# MSP430.net
KiCad netlist of a schematic drawn in Altium Designer
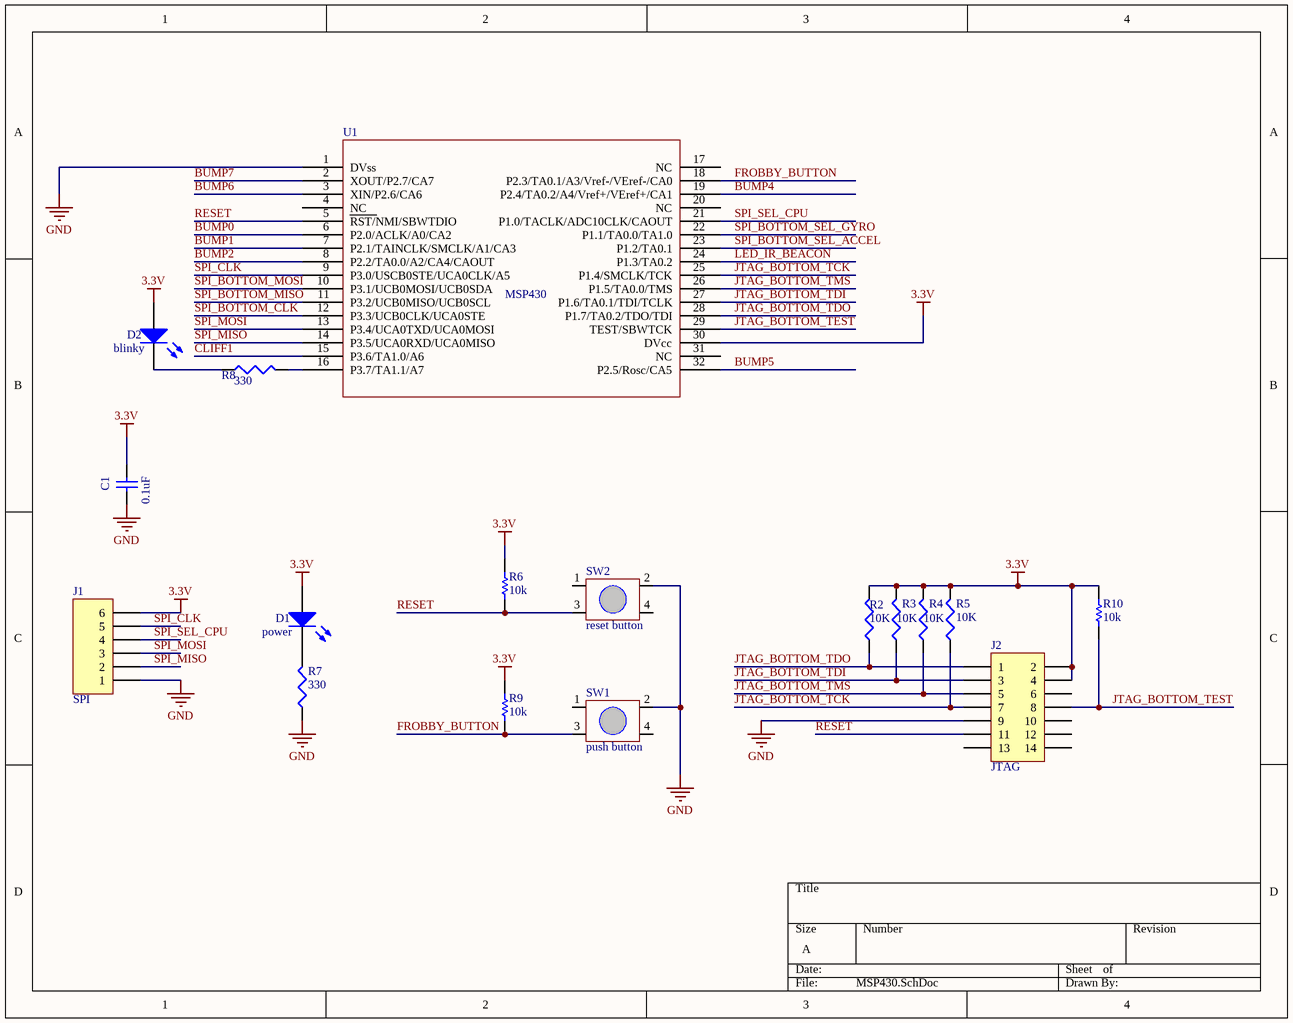
[diagram p0: MSP430.SchDoc]

(export (version "E")
  (design (tool "Eeschema 10.0.6"))
  (components
    (comp (ref "C1")
      (value "0.1uF")
      (footprint "CAPC1005L")
      (description "Capacitor (Semiconductor SIM Model)")
      (fields (field (name "Comment") "Cap Semi") (field (name "PUBLISHER") "Altium Limited"))
      (libsource (lib "Miscellaneous Devices") (part "Cap Semi"))
    )
    (comp (ref "D1") (value "power") (footprint "INDC2012L") (libsource (lib "mrone") (part "LED")))
    (comp (ref "D2") (value "blinky") (footprint "INDC2012L") (libsource (lib "mrone") (part "LED")))
    (comp (ref "J1")
      (value "SPI")
      (footprint "HDR1X6")
      (description "Header, 6-Pin")
      (fields (field (name "PUBLISHER") "Altium Limited"))
      (libsource (lib "Miscellaneous Connectors") (part "Header 6"))
    )
    (comp (ref "J2")
      (value "JTAG")
      (footprint "HDR2X7")
      (description "Header, 7-Pin, Dual row")
      (fields (field (name "PUBLISHER") "Altium Limited"))
      (libsource (lib "Miscellaneous Connectors") (part "Header 7X2"))
    )
    (comp (ref "R2")
      (value "10K")
      (footprint "RESC1608L")
      (description "Resistor")
      (fields (field (name "Comment") "Res3") (field (name "PUBLISHER") "Altium Limited"))
      (libsource (lib "Miscellaneous Devices") (part "Res3"))
    )
    (comp (ref "R3")
      (value "10K")
      (footprint "RESC1608L")
      (description "Resistor")
      (fields (field (name "Comment") "Res3") (field (name "PUBLISHER") "Altium Limited"))
      (libsource (lib "Miscellaneous Devices") (part "Res3"))
    )
    (comp (ref "R4")
      (value "10K")
      (footprint "RESC1608L")
      (description "Resistor")
      (fields (field (name "Comment") "Res3") (field (name "PUBLISHER") "Altium Limited"))
      (libsource (lib "Miscellaneous Devices") (part "Res3"))
    )
    (comp (ref "R5")
      (value "10K")
      (footprint "RESC1608L")
      (description "Resistor")
      (fields (field (name "Comment") "Res3") (field (name "PUBLISHER") "Altium Limited"))
      (libsource (lib "Miscellaneous Devices") (part "Res3"))
    )
    (comp (ref "R6")
      (value "10k")
      (footprint "RESC1608L")
      (description "Semiconductor Resistor")
      (fields (field (name "Comment") "Res Semi") (field (name "PUBLISHER") "Altium Limited"))
      (libsource (lib "Miscellaneous Devices") (part "Res Semi"))
    )
    (comp (ref "R7")
      (value "330")
      (footprint "RESC1608L")
      (description "Resistor")
      (fields (field (name "PUBLISHER") "Altium Limited"))
      (libsource (lib "Miscellaneous Devices") (part "Res3"))
    )
    (comp (ref "R8")
      (value "330")
      (footprint "RESC1608L")
      (description "Resistor")
      (fields (field (name "PUBLISHER") "Altium Limited"))
      (libsource (lib "Miscellaneous Devices") (part "Res3"))
    )
    (comp (ref "R9")
      (value "10k")
      (footprint "RESC1608L")
      (description "Semiconductor Resistor")
      (fields (field (name "Comment") "Res Semi") (field (name "PUBLISHER") "Altium Limited"))
      (libsource (lib "Miscellaneous Devices") (part "Res Semi"))
    )
    (comp (ref "R10")
      (value "10k")
      (footprint "RESC1608L")
      (description "Semiconductor Resistor")
      (fields (field (name "Comment") "Res Semi") (field (name "PUBLISHER") "Altium Limited"))
      (libsource (lib "Miscellaneous Devices") (part "Res Semi"))
    )
    (comp (ref "SW1")
      (value "push button")
      (footprint "SwitchTall-TL330")
      (libsource (lib "mrone") (part "Switch-TL330"))
    )
    (comp (ref "SW2")
      (value "reset button")
      (footprint "SwitchTall-TL330")
      (libsource (lib "mrone") (part "Switch-TL330"))
    )
    (comp (ref "U1")
      (value "MSP430")
      (footprint "MSP430_32PIN")
      (libsource (lib "mrone") (part "MSP430_32pin"))
    )
  )
  (nets
    (net (code "1") (name "/BUMP0") (class "Default")
      (node (ref "U1") (pin "6") (pinfunction "P2.0/ACLK/A0/CA2_6") (pintype "passive"))
    )
    (net (code "2") (name "/BUMP1") (class "Default")
      (node (ref "U1") (pin "7") (pinfunction "P2.1/TAINCLK/SMCLK/A1/CA3_7") (pintype "passive"))
    )
    (net (code "3") (name "/BUMP2") (class "Default")
      (node (ref "U1") (pin "8") (pinfunction "P2.2/TA0.0/A2/CA4/CAOUT_8") (pintype "passive"))
    )
    (net (code "4") (name "/BUMP4") (class "Default")
      (node (ref "U1") (pin "19") (pinfunction "P2.4/TA0.2/A4/Vref+/VEref+/CA1_19") (pintype "passive"))
    )
    (net (code "5") (name "/BUMP5") (class "Default")
      (node (ref "U1") (pin "32") (pinfunction "P2.5/Rosc/CA5_32") (pintype "passive"))
    )
    (net (code "6") (name "/BUMP6") (class "Default")
      (node (ref "U1") (pin "3") (pinfunction "XIN/P2.6/CA6_3") (pintype "passive"))
    )
    (net (code "7") (name "/BUMP7") (class "Default")
      (node (ref "U1") (pin "2") (pinfunction "XOUT/P2.7/CA7_2") (pintype "passive"))
    )
    (net (code "8") (name "/CLIFF1") (class "Default")
      (node (ref "U1") (pin "15") (pinfunction "P3.6/TA1.0/A6_15") (pintype "passive"))
    )
    (net (code "9") (name "/FROBBY_BUTTON") (class "Default")
      (node (ref "R9") (pin "1") (pinfunction "1_1") (pintype "passive"))
      (node (ref "SW1") (pin "3") (pinfunction "3_3") (pintype "passive"))
      (node (ref "U1") (pin "18") (pinfunction "P2.3/TA0.1/A3/Vref-/VEref-/CA0_18") (pintype "passive"))
    )
    (net (code "10") (name "/JTAG_BOTTOM_TCK") (class "Default")
      (node (ref "J2") (pin "7") (pinfunction "7_7") (pintype "passive"))
      (node (ref "R5") (pin "1") (pinfunction "1_1") (pintype "passive"))
      (node (ref "U1") (pin "25") (pinfunction "P1.4/SMCLK/TCK_25") (pintype "passive"))
    )
    (net (code "11") (name "/JTAG_BOTTOM_TDI") (class "Default")
      (node (ref "J2") (pin "3") (pinfunction "3_3") (pintype "passive"))
      (node (ref "R3") (pin "1") (pinfunction "1_1") (pintype "passive"))
      (node (ref "U1") (pin "27") (pinfunction "P1.6/TA0.1/TDI/TCLK_27") (pintype "passive"))
    )
    (net (code "12") (name "/JTAG_BOTTOM_TDO") (class "Default")
      (node (ref "J2") (pin "1") (pinfunction "1_1") (pintype "passive"))
      (node (ref "R2") (pin "1") (pinfunction "1_1") (pintype "passive"))
      (node (ref "U1") (pin "28") (pinfunction "P1.7/TA0.2/TDO/TDI_28") (pintype "passive"))
    )
    (net (code "13") (name "/JTAG_BOTTOM_TEST") (class "Default")
      (node (ref "J2") (pin "8") (pinfunction "8_8") (pintype "passive"))
      (node (ref "R10") (pin "1") (pinfunction "1_1") (pintype "passive"))
      (node (ref "U1") (pin "29") (pinfunction "TEST/SBWTCK_29") (pintype "passive"))
    )
    (net (code "14") (name "/JTAG_BOTTOM_TMS") (class "Default")
      (node (ref "J2") (pin "5") (pinfunction "5_5") (pintype "passive"))
      (node (ref "R4") (pin "1") (pinfunction "1_1") (pintype "passive"))
      (node (ref "U1") (pin "26") (pinfunction "P1.5/TA0.0/TMS_26") (pintype "passive"))
    )
    (net (code "15") (name "/LED_IR_BEACON") (class "Default")
      (node (ref "U1") (pin "24") (pinfunction "P1.3/TA0.2_24") (pintype "passive"))
    )
    (net (code "16") (name "/RESET") (class "Default")
      (node (ref "J2") (pin "11") (pinfunction "11_11") (pintype "passive"))
      (node (ref "R6") (pin "1") (pinfunction "1_1") (pintype "passive"))
      (node (ref "SW2") (pin "3") (pinfunction "3_3") (pintype "passive"))
      (node (ref "U1") (pin "5") (pinfunction "RST/NMI/SBWTDIO_5") (pintype "passive"))
    )
    (net (code "17") (name "/SPI_BOTTOM_CLK") (class "Default")
      (node (ref "U1") (pin "12") (pinfunction "P3.3/UCB0CLK/UCA0STE_12") (pintype "passive"))
    )
    (net (code "18") (name "/SPI_BOTTOM_MISO") (class "Default")
      (node (ref "U1") (pin "11") (pinfunction "P3.2/UCB0MISO/UCB0SCL_11") (pintype "passive"))
    )
    (net (code "19") (name "/SPI_BOTTOM_MOSI") (class "Default")
      (node (ref "U1") (pin "10") (pinfunction "P3.1/UCB0MOSI/UCB0SDA_10") (pintype "passive"))
    )
    (net (code "20") (name "/SPI_BOTTOM_SEL_ACCEL") (class "Default")
      (node (ref "U1") (pin "23") (pinfunction "P1.2/TA0.1_23") (pintype "passive"))
    )
    (net (code "21") (name "/SPI_BOTTOM_SEL_GYRO") (class "Default")
      (node (ref "U1") (pin "22") (pinfunction "P1.1/TA0.0/TA1.0_22") (pintype "passive"))
    )
    (net (code "22") (name "/SPI_CLK") (class "Default")
      (node (ref "J1") (pin "5") (pinfunction "5_5") (pintype "passive"))
      (node (ref "U1") (pin "9") (pinfunction "P3.0/USCB0STE/UCA0CLK/A5_9") (pintype "passive"))
    )
    (net (code "23") (name "/SPI_MISO") (class "Default")
      (node (ref "J1") (pin "2") (pinfunction "2_2") (pintype "passive"))
      (node (ref "U1") (pin "14") (pinfunction "P3.5/UCA0RXD/UCA0MISO_14") (pintype "passive"))
    )
    (net (code "24") (name "/SPI_MOSI") (class "Default")
      (node (ref "J1") (pin "3") (pinfunction "3_3") (pintype "passive"))
      (node (ref "U1") (pin "13") (pinfunction "P3.4/UCA0TXD/UCA0MOSI_13") (pintype "passive"))
    )
    (net (code "25") (name "/SPI_SEL_CPU") (class "Default")
      (node (ref "J1") (pin "4") (pinfunction "4_4") (pintype "passive"))
      (node (ref "U1") (pin "21") (pinfunction "P1.0/TACLK/ADC10CLK/CAOUT_21") (pintype "passive"))
    )
    (net (code "26") (name "3.3V") (class "Default")
      (node (ref "C1") (pin "2") (pinfunction "2_2") (pintype "passive"))
      (node (ref "D1") (pin "1") (pinfunction "A_1") (pintype "passive"))
      (node (ref "D2") (pin "1") (pinfunction "A_1") (pintype "passive"))
      (node (ref "J1") (pin "6") (pinfunction "6_6") (pintype "passive"))
      (node (ref "J2") (pin "2") (pinfunction "2_2") (pintype "passive"))
      (node (ref "J2") (pin "4") (pinfunction "4_4") (pintype "passive"))
      (node (ref "R10") (pin "2") (pinfunction "2_2") (pintype "passive"))
      (node (ref "R2") (pin "2") (pinfunction "2_2") (pintype "passive"))
      (node (ref "R3") (pin "2") (pinfunction "2_2") (pintype "passive"))
      (node (ref "R4") (pin "2") (pinfunction "2_2") (pintype "passive"))
      (node (ref "R5") (pin "2") (pinfunction "2_2") (pintype "passive"))
      (node (ref "R6") (pin "2") (pinfunction "2_2") (pintype "passive"))
      (node (ref "R9") (pin "2") (pinfunction "2_2") (pintype "passive"))
      (node (ref "U1") (pin "30") (pinfunction "DVcc_30") (pintype "passive"))
    )
    (net (code "27") (name "GND") (class "Default")
      (node (ref "C1") (pin "1") (pinfunction "1_1") (pintype "passive"))
      (node (ref "J1") (pin "1") (pinfunction "1_1") (pintype "passive"))
      (node (ref "J2") (pin "9") (pinfunction "9_9") (pintype "passive"))
      (node (ref "R7") (pin "1") (pinfunction "1_1") (pintype "passive"))
      (node (ref "SW1") (pin "2") (pinfunction "2_2") (pintype "passive"))
      (node (ref "SW2") (pin "2") (pinfunction "2_2") (pintype "passive"))
      (node (ref "U1") (pin "1") (pinfunction "DVss_1") (pintype "passive"))
    )
    (net (code "28") (name "Net-(D1-K)") (class "Default")
      (node (ref "D1") (pin "2") (pinfunction "K_2") (pintype "passive"))
      (node (ref "R7") (pin "2") (pinfunction "2_2") (pintype "passive"))
    )
    (net (code "29") (name "Net-(D2-K)") (class "Default")
      (node (ref "D2") (pin "2") (pinfunction "K_2") (pintype "passive"))
      (node (ref "R8") (pin "1") (pinfunction "1_1") (pintype "passive"))
    )
    (net (code "30") (name "Net-(U1-P3.7{slash}TA1.1{slash}A7)") (class "Default")
      (node (ref "R8") (pin "2") (pinfunction "2_2") (pintype "passive"))
      (node (ref "U1") (pin "16") (pinfunction "P3.7/TA1.1/A7_16") (pintype "passive"))
    )
    (net (code "31") (name "unconnected-(J2-Pad6)") (class "Default")
      (node (ref "J2") (pin "6") (pinfunction "6_6") (pintype "passive"))
    )
    (net (code "32") (name "unconnected-(J2-Pad10)") (class "Default")
      (node (ref "J2") (pin "10") (pinfunction "10_10") (pintype "passive"))
    )
    (net (code "33") (name "unconnected-(J2-Pad12)") (class "Default")
      (node (ref "J2") (pin "12") (pinfunction "12_12") (pintype "passive"))
    )
    (net (code "34") (name "unconnected-(J2-Pad13)") (class "Default")
      (node (ref "J2") (pin "13") (pinfunction "13_13") (pintype "passive"))
    )
    (net (code "35") (name "unconnected-(J2-Pad14)") (class "Default")
      (node (ref "J2") (pin "14") (pinfunction "14_14") (pintype "passive"))
    )
    (net (code "36") (name "unconnected-(SW1-Pad1)") (class "Default")
      (node (ref "SW1") (pin "1") (pinfunction "1_1") (pintype "passive"))
    )
    (net (code "37") (name "unconnected-(SW1-Pad4)") (class "Default")
      (node (ref "SW1") (pin "4") (pinfunction "4_4") (pintype "passive"))
    )
    (net (code "38") (name "unconnected-(SW2-Pad1)") (class "Default")
      (node (ref "SW2") (pin "1") (pinfunction "1_1") (pintype "passive"))
    )
    (net (code "39") (name "unconnected-(SW2-Pad4)") (class "Default")
      (node (ref "SW2") (pin "4") (pinfunction "4_4") (pintype "passive"))
    )
    (net (code "40") (name "unconnected-(U1-NC-Pad4)") (class "Default")
      (node (ref "U1") (pin "4") (pinfunction "NC_4") (pintype "passive"))
    )
    (net (code "41") (name "unconnected-(U1-NC-Pad17)") (class "Default")
      (node (ref "U1") (pin "17") (pinfunction "NC_17") (pintype "passive"))
    )
    (net (code "42") (name "unconnected-(U1-NC-Pad20)") (class "Default")
      (node (ref "U1") (pin "20") (pinfunction "NC_20") (pintype "passive"))
    )
    (net (code "43") (name "unconnected-(U1-NC-Pad31)") (class "Default")
      (node (ref "U1") (pin "31") (pinfunction "NC_31") (pintype "passive"))
    )
  )
)
